# Power7V4.net
KiCad netlist of a schematic drawn in Altium Designer
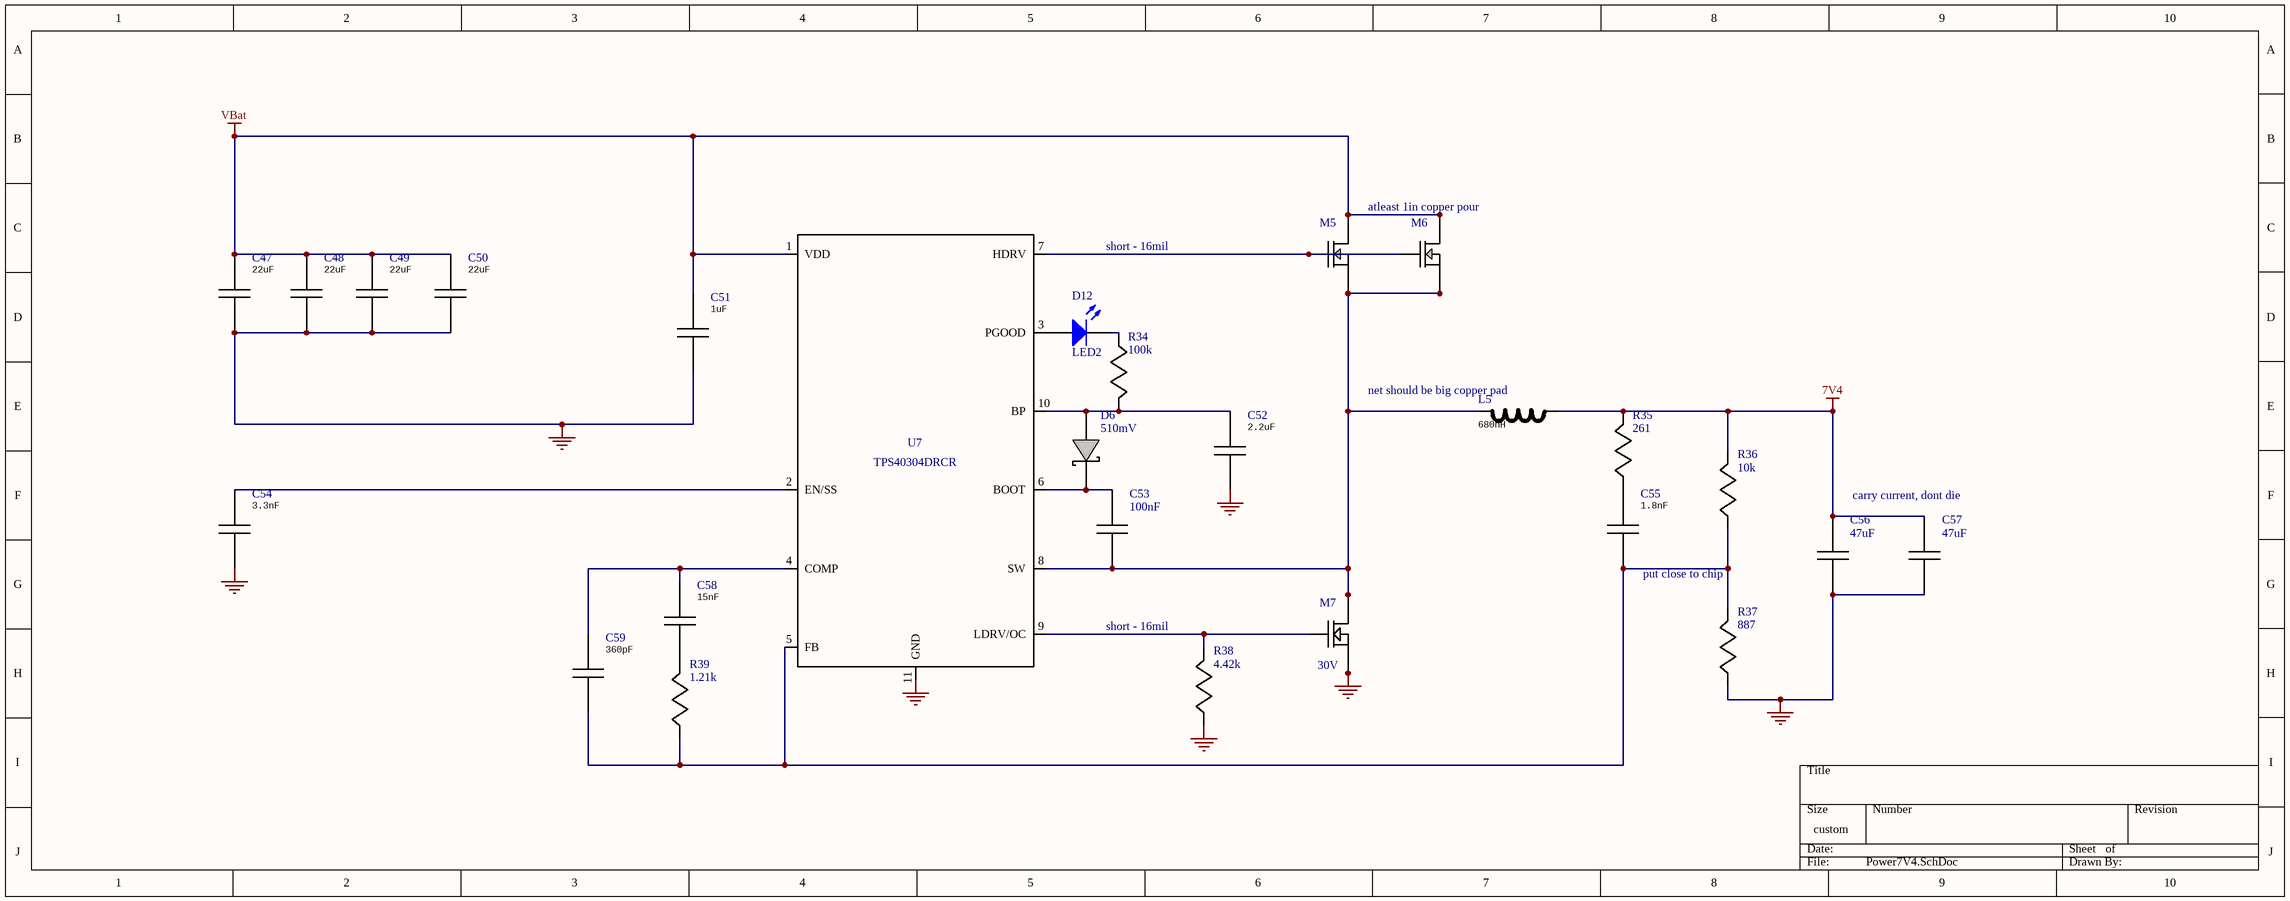
[diagram p0: Power7V4.SchDoc]

(export (version "E")
  (design (tool "Eeschema 10.0.6"))
  (components
    (comp (ref "C47")
      (value "22uF")
      (footprint "1210")
      (description "Imported")
      (fields
        (field (name "MANUFACTURER_PART_NUMBER") "GRM32ER61E226KE15L")
        (field (name "Comment") "GRM32ER61E226KE1")
      )
      (libsource (lib "TI WEBENCH") (part "GRM32ER61E226KE1"))
    )
    (comp (ref "C48")
      (value "22uF")
      (footprint "1210")
      (description "Imported")
      (fields
        (field (name "MANUFACTURER_PART_NUMBER") "GRM32ER61E226KE15L")
        (field (name "Comment") "GRM32ER61E226KE1")
      )
      (libsource (lib "TI WEBENCH") (part "GRM32ER61E226KE1"))
    )
    (comp (ref "C49")
      (value "22uF")
      (footprint "1210")
      (description "Imported")
      (fields
        (field (name "MANUFACTURER_PART_NUMBER") "GRM32ER61E226KE15L")
        (field (name "Comment") "GRM32ER61E226KE1")
      )
      (libsource (lib "TI WEBENCH") (part "GRM32ER61E226KE1"))
    )
    (comp (ref "C50")
      (value "22uF")
      (footprint "1210")
      (description "Imported")
      (fields
        (field (name "MANUFACTURER_PART_NUMBER") "GRM32ER61E226KE15L")
        (field (name "Comment") "GRM32ER61E226KE1")
      )
      (libsource (lib "TI WEBENCH") (part "GRM32ER61E226KE1"))
    )
    (comp (ref "C51")
      (value "1uF")
      (footprint "1608")
      (description "Imported")
      (fields
        (field (name "MANUFACTURER_PART_NUMBER") "GRM188R61E105KA12D")
        (field (name "Comment") "GRM188R61E105KA1")
      )
      (libsource (lib "TI WEBENCH") (part "GRM188R61E105KA1"))
    )
    (comp (ref "C52")
      (value "2.2uF")
      (footprint "1608")
      (description "Imported")
      (fields
        (field (name "MANUFACTURER_PART_NUMBER") "GRM188R61A225KE34D")
        (field (name "Comment") "GRM188R61A225KE3")
      )
      (libsource (lib "TI WEBENCH") (part "GRM188R61A225KE3"))
    )
    (comp (ref "C53")
      (value "100nF")
      (footprint "1608")
      (description "08053C104KAT2A")
      (libsource (lib "TI WEBENCH") (part "08053C104KAT2A"))
    )
    (comp (ref "C54")
      (value "3.3nF")
      (footprint "1608")
      (description "Imported")
      (fields
        (field (name "MANUFACTURER_PART_NUMBER") "GRM033R71C332KA88D")
        (field (name "Comment") "GRM033R71C332KA8")
      )
      (libsource (lib "TI WEBENCH") (part "GRM033R71C332KA8"))
    )
    (comp (ref "C55")
      (value "1.8nF")
      (footprint "1608")
      (description "Imported")
      (fields
        (field (name "MANUFACTURER_PART_NUMBER") "GRM155R71H182KA01D")
        (field (name "Comment") "GRM155R71H182KA0")
      )
      (libsource (lib "TI WEBENCH") (part "GRM155R71H182KA0"))
    )
    (comp (ref "C56")
      (value "47uF")
      (footprint "1206")
      (description "C3216X6S1A476M")
      (libsource (lib "TI WEBENCH") (part "C3216X6S1A476M"))
    )
    (comp (ref "C57")
      (value "47uF")
      (footprint "1206")
      (description "C3216X6S1A476M")
      (libsource (lib "TI WEBENCH") (part "C3216X6S1A476M"))
    )
    (comp (ref "C58")
      (value "15nF")
      (footprint "1608")
      (description "Imported")
      (fields
        (field (name "MANUFACTURER_PART_NUMBER") "CC0805KRX7R9BB153")
        (field (name "Comment") "CC0805KRX7R9BB15")
      )
      (libsource (lib "TI WEBENCH") (part "CC0805KRX7R9BB15"))
    )
    (comp (ref "C59")
      (value "360pF")
      (footprint "1608")
      (description "Imported")
      (fields
        (field (name "MANUFACTURER_PART_NUMBER") "GRM1555C1H361JA01D")
        (field (name "Comment") "GRM1555C1H361JA0")
      )
      (libsource (lib "TI WEBENCH") (part "GRM1555C1H361JA0"))
    )
    (comp (ref "D6")
      (value "510mV")
      (footprint "SOD-123")
      (description "MBR0540T1G")
      (libsource (lib "TI WEBENCH") (part "MBR0540T1G"))
    )
    (comp (ref "D12")
      (value "LED2")
      (footprint "1608[0603]")
      (description "Typical RED, GREEN, YELLOW, AMBER GaAs LED")
      (fields (field (name "PUBLISHER") "Altium Limited"))
      (libsource (lib "Miscellaneous Devices") (part "LED2"))
    )
    (comp (ref "L5")
      (value "680nH")
      (footprint "XAL1010")
      (description "Imported")
      (fields
        (field (name "MANUFACTURER_PART_NUMBER") "XAL1010-451MEB")
        (field (name "Comment") "XAL1010-681MEB")
      )
      (libsource (lib "TI WEBENCH") (part "XAL1010-681MEB"))
    )
    (comp (ref "M5")
      (value "CSD16340Q3")
      (footprint "TRANS_NexFET_Q3")
      (description "Imported")
      (libsource (lib "TI WEBENCH") (part "CSD16340Q3"))
    )
    (comp (ref "M6")
      (value "CSD16340Q3")
      (footprint "TRANS_NexFET_Q3")
      (description "Imported")
      (libsource (lib "TI WEBENCH") (part "CSD16340Q3"))
    )
    (comp (ref "M7")
      (value "30V")
      (footprint "PG-TSDSON-8")
      (description "BSZ050N03MS G")
      (libsource (lib "TI WEBENCH") (part "BSZ050N03MS G"))
    )
    (comp (ref "R34")
      (value "100k")
      (footprint "1608")
      (description "CRCW0402100KFKED")
      (libsource (lib "TI WEBENCH") (part "CRCW0402100KFKED"))
    )
    (comp (ref "R35")
      (value "261")
      (footprint "1608")
      (description "CRCW0402261RFKED")
      (libsource (lib "TI WEBENCH") (part "CRCW0402261RFKED"))
    )
    (comp (ref "R36")
      (value "10k")
      (footprint "1608")
      (description "CRCW040210K0FKED")
      (libsource (lib "TI WEBENCH") (part "CRCW040210K0FKED"))
    )
    (comp (ref "R37")
      (value "887")
      (footprint "1608")
      (description "CRCW0402887RFKED")
      (libsource (lib "TI WEBENCH") (part "CRCW0402887RFKED"))
    )
    (comp (ref "R38")
      (value "4.42k")
      (footprint "1608")
      (description "CRCW04024K42FKED")
      (libsource (lib "TI WEBENCH") (part "CRCW04024K42FKED"))
    )
    (comp (ref "R39")
      (value "1.21k")
      (footprint "1608")
      (description "CRCW04021K21FKED")
      (libsource (lib "TI WEBENCH") (part "CRCW04021K21FKED"))
    )
    (comp (ref "U7")
      (value "TPS40304DRCR")
      (footprint "S-PVSON-N10")
      (fields (field (name "PACKAGEREFERENCE") "TPS40304DRCR"))
      (libsource (lib "TI WEBENCH") (part "TPS40304DRCR"))
    )
  )
  (nets
    (net (code "1") (name "7V4") (class "Default")
      (node (ref "C56") (pin "1") (pinfunction "1_1") (pintype "passive"))
      (node (ref "C57") (pin "1") (pinfunction "1_1") (pintype "passive"))
      (node (ref "L5") (pin "2") (pinfunction "2_2") (pintype "passive"))
      (node (ref "R35") (pin "1") (pinfunction "1_1") (pintype "passive"))
      (node (ref "R36") (pin "1") (pinfunction "1_1") (pintype "passive"))
    )
    (net (code "2") (name "GND") (class "Default")
      (node (ref "C47") (pin "2") (pinfunction "2_2") (pintype "passive"))
      (node (ref "C48") (pin "2") (pinfunction "2_2") (pintype "passive"))
      (node (ref "C49") (pin "2") (pinfunction "2_2") (pintype "passive"))
      (node (ref "C50") (pin "2") (pinfunction "2_2") (pintype "passive"))
      (node (ref "C51") (pin "2") (pinfunction "2_2") (pintype "passive"))
      (node (ref "C52") (pin "2") (pinfunction "2_2") (pintype "passive"))
      (node (ref "C54") (pin "2") (pinfunction "2_2") (pintype "passive"))
      (node (ref "C56") (pin "2") (pinfunction "2_2") (pintype "passive"))
      (node (ref "C57") (pin "2") (pinfunction "2_2") (pintype "passive"))
      (node (ref "M7") (pin "1") (pinfunction "Source_1") (pintype "passive"))
      (node (ref "M7") (pin "2") (pinfunction "Source_2") (pintype "passive"))
      (node (ref "M7") (pin "3") (pinfunction "Source_3") (pintype "passive"))
      (node (ref "R37") (pin "2") (pinfunction "2_2") (pintype "passive"))
      (node (ref "R38") (pin "2") (pinfunction "2_2") (pintype "passive"))
      (node (ref "U7") (pin "11") (pinfunction "GND_11") (pintype "passive"))
    )
    (net (code "3") (name "Net-(C55-Pad1)") (class "Default")
      (node (ref "C55") (pin "1") (pinfunction "1_1") (pintype "passive"))
      (node (ref "R35") (pin "2") (pinfunction "2_2") (pintype "passive"))
    )
    (net (code "4") (name "Net-(C58-Pad1)") (class "Default")
      (node (ref "C58") (pin "1") (pinfunction "1_1") (pintype "passive"))
      (node (ref "R39") (pin "1") (pinfunction "1_1") (pintype "passive"))
    )
    (net (code "5") (name "Net-(D6-A)") (class "Default")
      (node (ref "C52") (pin "1") (pinfunction "1_1") (pintype "passive"))
      (node (ref "D6") (pin "2") (pinfunction "A_2") (pintype "passive"))
      (node (ref "R34") (pin "1") (pinfunction "1_1") (pintype "passive"))
      (node (ref "U7") (pin "10") (pinfunction "BP_10") (pintype "passive"))
    )
    (net (code "6") (name "Net-(D6-K)") (class "Default")
      (node (ref "C53") (pin "1") (pinfunction "1_1") (pintype "passive"))
      (node (ref "D6") (pin "1") (pinfunction "K_1") (pintype "passive"))
      (node (ref "U7") (pin "6") (pinfunction "BOOT_6") (pintype "passive"))
    )
    (net (code "7") (name "Net-(D12-A)") (class "Default")
      (node (ref "D12") (pin "1") (pinfunction "A_1") (pintype "passive"))
      (node (ref "U7") (pin "3") (pinfunction "PGOOD_3") (pintype "passive"))
    )
    (net (code "8") (name "Net-(D12-K)") (class "Default")
      (node (ref "D12") (pin "2") (pinfunction "K_2") (pintype "passive"))
      (node (ref "R34") (pin "2") (pinfunction "2_2") (pintype "passive"))
    )
    (net (code "9") (name "Net-(M5-Gate)") (class "Default")
      (node (ref "M5") (pin "4") (pinfunction "Gate_4") (pintype "passive"))
      (node (ref "M6") (pin "4") (pinfunction "Gate_4") (pintype "passive"))
      (node (ref "U7") (pin "7") (pinfunction "HDRV_7") (pintype "passive"))
    )
    (net (code "10") (name "Net-(M7-Gate)") (class "Default")
      (node (ref "M7") (pin "4") (pinfunction "Gate_4") (pintype "passive"))
      (node (ref "R38") (pin "1") (pinfunction "1_1") (pintype "passive"))
      (node (ref "U7") (pin "9") (pinfunction "LDRV/OC_9") (pintype "passive"))
    )
    (net (code "11") (name "Net-(U7-COMP)") (class "Default")
      (node (ref "C58") (pin "2") (pinfunction "2_2") (pintype "passive"))
      (node (ref "C59") (pin "2") (pinfunction "2_2") (pintype "passive"))
      (node (ref "U7") (pin "4") (pinfunction "COMP_4") (pintype "passive"))
    )
    (net (code "12") (name "Net-(U7-EN{slash}SS)") (class "Default")
      (node (ref "C54") (pin "1") (pinfunction "1_1") (pintype "passive"))
      (node (ref "U7") (pin "2") (pinfunction "EN/SS_2") (pintype "passive"))
    )
    (net (code "13") (name "Net-(U7-FB)") (class "Default")
      (node (ref "C55") (pin "2") (pinfunction "2_2") (pintype "passive"))
      (node (ref "C59") (pin "1") (pinfunction "1_1") (pintype "passive"))
      (node (ref "R36") (pin "2") (pinfunction "2_2") (pintype "passive"))
      (node (ref "R37") (pin "1") (pinfunction "1_1") (pintype "passive"))
      (node (ref "R39") (pin "2") (pinfunction "2_2") (pintype "passive"))
      (node (ref "U7") (pin "5") (pinfunction "FB_5") (pintype "passive"))
    )
    (net (code "14") (name "Net-(U7-SW)") (class "Default")
      (node (ref "C53") (pin "2") (pinfunction "2_2") (pintype "passive"))
      (node (ref "L5") (pin "1") (pinfunction "1_1") (pintype "passive"))
      (node (ref "M5") (pin "1") (pinfunction "Source_1") (pintype "passive"))
      (node (ref "M5") (pin "2") (pinfunction "Source_2") (pintype "passive"))
      (node (ref "M5") (pin "3") (pinfunction "Source_3") (pintype "passive"))
      (node (ref "M6") (pin "1") (pinfunction "Source_1") (pintype "passive"))
      (node (ref "M6") (pin "2") (pinfunction "Source_2") (pintype "passive"))
      (node (ref "M6") (pin "3") (pinfunction "Source_3") (pintype "passive"))
      (node (ref "M7") (pin "5") (pinfunction "Drain_5") (pintype "passive"))
      (node (ref "M7") (pin "6") (pinfunction "Drain_6") (pintype "passive"))
      (node (ref "M7") (pin "7") (pinfunction "Drain_7") (pintype "passive"))
      (node (ref "M7") (pin "8") (pinfunction "Drain_8") (pintype "passive"))
      (node (ref "M7") (pin "9") (pinfunction "Drain_9") (pintype "passive"))
      (node (ref "U7") (pin "8") (pinfunction "SW_8") (pintype "passive"))
    )
    (net (code "15") (name "VBat") (class "Default")
      (node (ref "C47") (pin "1") (pinfunction "1_1") (pintype "passive"))
      (node (ref "C48") (pin "1") (pinfunction "1_1") (pintype "passive"))
      (node (ref "C49") (pin "1") (pinfunction "1_1") (pintype "passive"))
      (node (ref "C50") (pin "1") (pinfunction "1_1") (pintype "passive"))
      (node (ref "C51") (pin "1") (pinfunction "1_1") (pintype "passive"))
      (node (ref "M5") (pin "5") (pinfunction "Drain_5") (pintype "passive"))
      (node (ref "M5") (pin "6") (pinfunction "Drain_6") (pintype "passive"))
      (node (ref "M5") (pin "7") (pinfunction "Drain_7") (pintype "passive"))
      (node (ref "M5") (pin "8") (pinfunction "Drain_8") (pintype "passive"))
      (node (ref "M5") (pin "9") (pinfunction "Drain_9") (pintype "passive"))
      (node (ref "M6") (pin "5") (pinfunction "Drain_5") (pintype "passive"))
      (node (ref "M6") (pin "6") (pinfunction "Drain_6") (pintype "passive"))
      (node (ref "M6") (pin "7") (pinfunction "Drain_7") (pintype "passive"))
      (node (ref "M6") (pin "8") (pinfunction "Drain_8") (pintype "passive"))
      (node (ref "M6") (pin "9") (pinfunction "Drain_9") (pintype "passive"))
      (node (ref "U7") (pin "1") (pinfunction "VDD_1") (pintype "passive"))
    )
  )
)
